# cs301_07b.net
KiCad netlist of a schematic drawn in Altium Designer
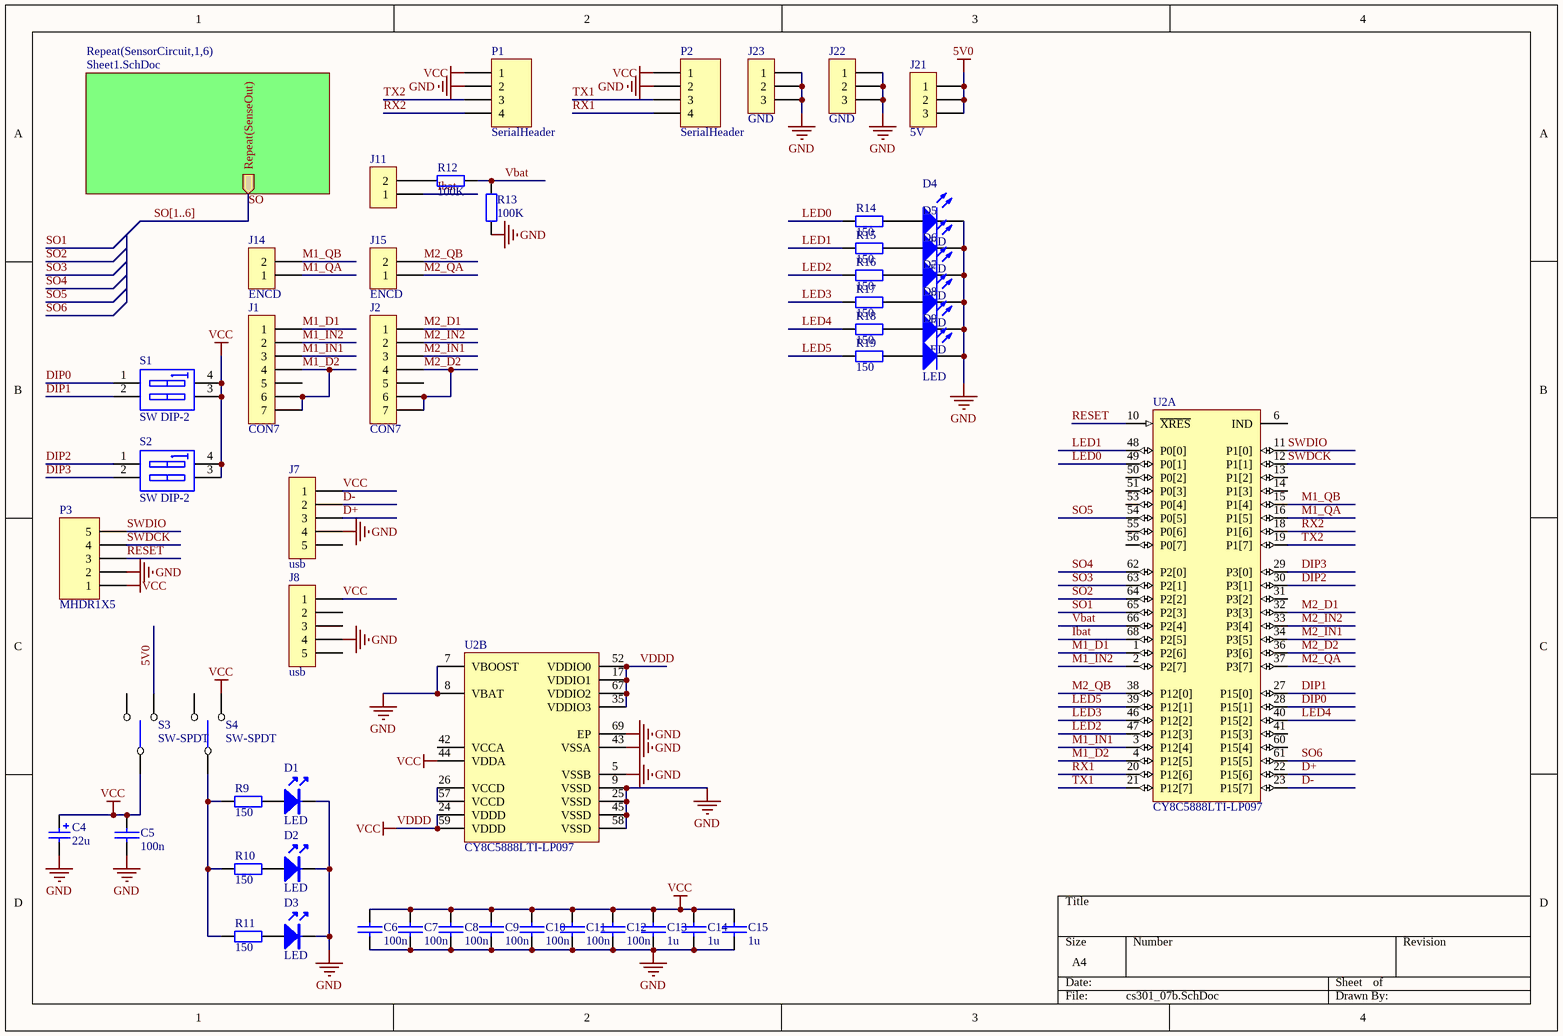
[diagram p0: cs301_07b.SchDoc]

(export (version "E")
  (design (tool "Eeschema 10.0.6"))
  (components
    (comp (ref "C4")
      (value "22u")
      (footprint "ECE-CAPAE6.3X5.4SM")
      (description "CAP 22uF 35V ELE SM")
      (libsource (lib "EceParts") (part "Cap Pol"))
    )
    (comp (ref "C5")
      (value "100n")
      (footprint "ECE-CAPC1608-0603SM")
      (description "CAP CER 100nF 25V X7R SM0603")
      (libsource (lib "EceParts") (part "Cap"))
    )
    (comp (ref "C6")
      (value "100n")
      (footprint "ECE-CAPC1608-0603SM")
      (description "CAP CER 100nF 25V X7R SM0603")
      (libsource (lib "EceParts") (part "Cap"))
    )
    (comp (ref "C7")
      (value "100n")
      (footprint "ECE-CAPC1608-0603SM")
      (description "CAP CER 100nF 25V X7R SM0603")
      (libsource (lib "EceParts") (part "Cap"))
    )
    (comp (ref "C8")
      (value "100n")
      (footprint "ECE-CAPC1608-0603SM")
      (description "CAP CER 100nF 25V X7R SM0603")
      (libsource (lib "EceParts") (part "Cap"))
    )
    (comp (ref "C9")
      (value "100n")
      (footprint "ECE-CAPC1608-0603SM")
      (description "CAP CER 100nF 25V X7R SM0603")
      (libsource (lib "EceParts") (part "Cap"))
    )
    (comp (ref "C10")
      (value "100n")
      (footprint "ECE-CAPC1608-0603SM")
      (description "CAP CER 100nF 25V X7R SM0603")
      (libsource (lib "EceParts") (part "Cap"))
    )
    (comp (ref "C11")
      (value "100n")
      (footprint "ECE-CAPC1608-0603SM")
      (description "CAP CER 100nF 25V X7R SM0603")
      (libsource (lib "EceParts") (part "Cap"))
    )
    (comp (ref "C12")
      (value "100n")
      (footprint "ECE-CAPC1608-0603SM")
      (description "CAP CER 100nF 25V X7R SM0603")
      (libsource (lib "EceParts") (part "Cap"))
    )
    (comp (ref "C13")
      (value "1u")
      (footprint "ECE-CAPC1608-0603SM")
      (description "CAP CER 1uF 50V X7R SM0603")
      (libsource (lib "EceParts") (part "Cap"))
    )
    (comp (ref "C14")
      (value "1u")
      (footprint "ECE-CAPC1608-0603SM")
      (description "CAP CER 1uF 50V X7R SM0603")
      (libsource (lib "EceParts") (part "Cap"))
    )
    (comp (ref "C15")
      (value "1u")
      (footprint "ECE-CAPC1608-0603SM")
      (description "CAP CER 1uF 50V X7R SM0603")
      (libsource (lib "EceParts") (part "Cap"))
    )
    (comp (ref "D1") (value "LED") (footprint "LED0.1/5MM") (libsource (lib "COMSYS301_2013") (part "LED")))
    (comp (ref "D2") (value "LED") (footprint "LED0.1/5MM") (libsource (lib "COMSYS301_2013") (part "LED")))
    (comp (ref "D3") (value "LED") (footprint "LED0.1/5MM") (libsource (lib "COMSYS301_2013") (part "LED")))
    (comp (ref "D4")
      (value "LED")
      (footprint "ECE-LED2012-0805SM")
      (description "LED RED ORANGE CLEAR 0805 SMD")
      (libsource (lib "EceParts") (part "LED"))
    )
    (comp (ref "D5")
      (value "LED")
      (footprint "ECE-LED2012-0805SM")
      (description "LED RED ORANGE CLEAR 0805 SMD")
      (libsource (lib "EceParts") (part "LED"))
    )
    (comp (ref "D6")
      (value "LED")
      (footprint "ECE-LED2012-0805SM")
      (description "LED RED ORANGE CLEAR 0805 SMD")
      (libsource (lib "EceParts") (part "LED"))
    )
    (comp (ref "D7")
      (value "LED")
      (footprint "ECE-LED2012-0805SM")
      (description "LED RED ORANGE CLEAR 0805 SMD")
      (libsource (lib "EceParts") (part "LED"))
    )
    (comp (ref "D8")
      (value "LED")
      (footprint "ECE-LED2012-0805SM")
      (description "LED RED ORANGE CLEAR 0805 SMD")
      (libsource (lib "EceParts") (part "LED"))
    )
    (comp (ref "D9")
      (value "LED")
      (footprint "ECE-LED2012-0805SM")
      (description "LED RED ORANGE CLEAR 0805 SMD")
      (libsource (lib "EceParts") (part "LED"))
    )
    (comp (ref "J1")
      (value "CON7")
      (footprint "SIP7")
      (description "Connector")
      (libsource (lib "Miscellaneous Devices") (part "CON7"))
    )
    (comp (ref "J2")
      (value "CON7")
      (footprint "SIP7")
      (description "Connector")
      (libsource (lib "Miscellaneous Devices") (part "CON7"))
    )
    (comp (ref "J7")
      (value "usb")
      (footprint "SIP5")
      (description "Connector")
      (libsource (lib "Miscellaneous Devices") (part "CON5"))
    )
    (comp (ref "J8")
      (value "usb")
      (footprint "SIP5")
      (description "Connector")
      (libsource (lib "Miscellaneous Devices") (part "CON5"))
    )
    (comp (ref "J11")
      (value "Battery")
      (footprint "sip2")
      (description "Connector")
      (libsource (lib "Miscellaneous Devices") (part "CON2"))
    )
    (comp (ref "J14")
      (value "ENCD")
      (footprint "sip2")
      (description "Connector")
      (libsource (lib "Miscellaneous Devices") (part "CON2"))
    )
    (comp (ref "J15")
      (value "ENCD")
      (footprint "sip2")
      (description "Connector")
      (libsource (lib "Miscellaneous Devices") (part "CON2"))
    )
    (comp (ref "J21")
      (value "5V")
      (footprint "sip3")
      (description "Connector")
      (libsource (lib "Miscellaneous Devices") (part "CON3"))
    )
    (comp (ref "J22")
      (value "GND")
      (footprint "sip3")
      (description "Connector")
      (libsource (lib "Miscellaneous Devices") (part "CON3"))
    )
    (comp (ref "J23")
      (value "GND")
      (footprint "sip3")
      (description "Connector")
      (libsource (lib "Miscellaneous Devices") (part "CON3"))
    )
    (comp (ref "P1")
      (value "SerialHeader")
      (footprint "HDR1X4")
      (description "Header, 4-Pin")
      (fields (field (name "PUBLISHER") "Altium Limited"))
      (libsource (lib "Miscellaneous Connectors") (part "Header 4"))
    )
    (comp (ref "P2")
      (value "SerialHeader")
      (footprint "HDR1X4")
      (description "Header, 4-Pin")
      (fields (field (name "PUBLISHER") "Altium Limited"))
      (libsource (lib "Miscellaneous Connectors") (part "Header 4"))
    )
    (comp (ref "P3")
      (value "MHDR1X5")
      (footprint "MHDR1X5")
      (description "Header, 5-Pin")
      (fields (field (name "PUBLISHER") "Altium Limited"))
      (libsource (lib "Miscellaneous Connectors") (part "MHDR1X5"))
    )
    (comp (ref "R9")
      (value "150")
      (footprint "ECE-RESC1608-0603SM")
      (description "RES CER 150R 1608 SM")
      (libsource (lib "EceParts") (part "Resistor"))
    )
    (comp (ref "R10")
      (value "150")
      (footprint "ECE-RESC1608-0603SM")
      (description "RES CER 150R 1608 SM")
      (libsource (lib "EceParts") (part "Resistor"))
    )
    (comp (ref "R11")
      (value "150")
      (footprint "ECE-RESC1608-0603SM")
      (description "RES CER 150R 1608 SM")
      (libsource (lib "EceParts") (part "Resistor"))
    )
    (comp (ref "R12")
      (value "100K")
      (footprint "ECE-RESC1608-0603SM")
      (description "RES CER 100K 1608 SM")
      (libsource (lib "EceParts") (part "Resistor"))
    )
    (comp (ref "R13")
      (value "100K")
      (footprint "ECE-RESC1608-0603SM")
      (description "RES CER 100K 1608 SM")
      (libsource (lib "") (part "Resistor_1"))
    )
    (comp (ref "R14")
      (value "150")
      (footprint "ECE-RESC1608-0603SM")
      (description "RES CER 150R 1608 SM")
      (libsource (lib "EceParts") (part "Resistor"))
    )
    (comp (ref "R15")
      (value "150")
      (footprint "ECE-RESC1608-0603SM")
      (description "RES CER 150R 1608 SM")
      (libsource (lib "EceParts") (part "Resistor"))
    )
    (comp (ref "R16")
      (value "150")
      (footprint "ECE-RESC1608-0603SM")
      (description "RES CER 150R 1608 SM")
      (libsource (lib "EceParts") (part "Resistor"))
    )
    (comp (ref "R17")
      (value "150")
      (footprint "ECE-RESC1608-0603SM")
      (description "RES CER 150R 1608 SM")
      (libsource (lib "EceParts") (part "Resistor"))
    )
    (comp (ref "R18")
      (value "150")
      (footprint "ECE-RESC1608-0603SM")
      (description "RES CER 150R 1608 SM")
      (libsource (lib "EceParts") (part "Resistor"))
    )
    (comp (ref "R19")
      (value "150")
      (footprint "ECE-RESC1608-0603SM")
      (description "RES CER 150R 1608 SM")
      (libsource (lib "EceParts") (part "Resistor"))
    )
    (comp (ref "S1")
      (value "SW DIP-2")
      (footprint "DIP-4")
      (description "DIP Switch, 2 Position, SPST")
      (fields (field (name "PUBLISHER") "Altium Limited"))
      (libsource (lib "Miscellaneous Devices") (part "SW DIP-2"))
    )
    (comp (ref "S2")
      (value "SW DIP-2")
      (footprint "DIP-4")
      (description "DIP Switch, 2 Position, SPST")
      (fields (field (name "PUBLISHER") "Altium Limited"))
      (libsource (lib "Miscellaneous Devices") (part "SW DIP-2"))
    )
    (comp (ref "S3")
      (value "SW-SPDT")
      (footprint "SW-SPDT")
      (description "Toggle Switch")
      (libsource (lib "COMSYS301_2013") (part "SW-SPDT"))
    )
    (comp (ref "S4")
      (value "SW-SPDT")
      (footprint "SW-SPDT")
      (description "Toggle Switch")
      (libsource (lib "COMSYS301_2013") (part "SW-SPDT"))
    )
    (comp (ref "U2")
      (value "CY8C5888LTI-LP097")
      (footprint "CYP-LTX68_N")
      (description "PSoC Programmable System-on-Chip, 256 KB Flash, 38 GPIOs, 1.71 to 5.5 V, 68-Pin QFN (LTX68), Tray")
      (fields (field (name "MANUFACTURER") "Cypress"))
      (libsource (lib "Cypress PSoC 5LP") (part "CY8C5888LTI-LP097"))
    )
  )
  (nets
    (net (code "1") (name "/D+") (class "Default")
      (node (ref "J7") (pin "3") (pinfunction "3_3") (pintype "passive"))
      (node (ref "U2") (pin "22") (pinfunction "P15[6]_22") (pintype "bidirectional"))
    )
    (net (code "2") (name "/D-") (class "Default")
      (node (ref "J7") (pin "2") (pinfunction "2_2") (pintype "passive"))
      (node (ref "U2") (pin "23") (pinfunction "P15[7]_23") (pintype "bidirectional"))
    )
    (net (code "3") (name "/DIP0") (class "Default")
      (node (ref "S1") (pin "1") (pinfunction "A1_1") (pintype "passive"))
      (node (ref "U2") (pin "28") (pinfunction "P15[1]_28") (pintype "bidirectional"))
    )
    (net (code "4") (name "/DIP1") (class "Default")
      (node (ref "S1") (pin "2") (pinfunction "A2_2") (pintype "passive"))
      (node (ref "U2") (pin "27") (pinfunction "P15[0]_27") (pintype "bidirectional"))
    )
    (net (code "5") (name "/DIP2") (class "Default")
      (node (ref "S2") (pin "1") (pinfunction "A1_1") (pintype "passive"))
      (node (ref "U2") (pin "30") (pinfunction "P3[1]_30") (pintype "bidirectional"))
    )
    (net (code "6") (name "/DIP3") (class "Default")
      (node (ref "S2") (pin "2") (pinfunction "A2_2") (pintype "passive"))
      (node (ref "U2") (pin "29") (pinfunction "P3[0]_29") (pintype "bidirectional"))
    )
    (net (code "7") (name "/Ibat") (class "Default")
      (node (ref "J11") (pin "1") (pinfunction "1_1") (pintype "passive"))
      (node (ref "U2") (pin "68") (pinfunction "P2[5]_68") (pintype "bidirectional"))
    )
    (net (code "8") (name "/LED0") (class "Default")
      (node (ref "R14") (pin "1") (pinfunction "1_1") (pintype "passive"))
      (node (ref "U2") (pin "49") (pinfunction "P0[1]_49") (pintype "bidirectional"))
    )
    (net (code "9") (name "/LED1") (class "Default")
      (node (ref "R15") (pin "1") (pinfunction "1_1") (pintype "passive"))
      (node (ref "U2") (pin "48") (pinfunction "P0[0]_48") (pintype "bidirectional"))
    )
    (net (code "10") (name "/LED2") (class "Default")
      (node (ref "R16") (pin "1") (pinfunction "1_1") (pintype "passive"))
      (node (ref "U2") (pin "47") (pinfunction "P12[3]_47") (pintype "bidirectional"))
    )
    (net (code "11") (name "/LED3") (class "Default")
      (node (ref "R17") (pin "1") (pinfunction "1_1") (pintype "passive"))
      (node (ref "U2") (pin "46") (pinfunction "P12[2]_46") (pintype "bidirectional"))
    )
    (net (code "12") (name "/LED4") (class "Default")
      (node (ref "R18") (pin "1") (pinfunction "1_1") (pintype "passive"))
      (node (ref "U2") (pin "40") (pinfunction "P15[2]_40") (pintype "bidirectional"))
    )
    (net (code "13") (name "/LED5") (class "Default")
      (node (ref "R19") (pin "1") (pinfunction "1_1") (pintype "passive"))
      (node (ref "U2") (pin "39") (pinfunction "P12[1]_39") (pintype "bidirectional"))
    )
    (net (code "14") (name "/M1_D1") (class "Default")
      (node (ref "J1") (pin "1") (pinfunction "1_1") (pintype "passive"))
      (node (ref "U2") (pin "1") (pinfunction "P2[6]_1") (pintype "bidirectional"))
    )
    (net (code "15") (name "/M1_D2") (class "Default")
      (node (ref "J1") (pin "4") (pinfunction "4_4") (pintype "passive"))
      (node (ref "J1") (pin "6") (pinfunction "6_6") (pintype "passive"))
      (node (ref "J1") (pin "7") (pinfunction "7_7") (pintype "passive"))
      (node (ref "U2") (pin "4") (pinfunction "P12[5]_4") (pintype "bidirectional"))
    )
    (net (code "16") (name "/M1_IN1") (class "Default")
      (node (ref "J1") (pin "3") (pinfunction "3_3") (pintype "passive"))
      (node (ref "U2") (pin "3") (pinfunction "P12[4]_3") (pintype "bidirectional"))
    )
    (net (code "17") (name "/M1_IN2") (class "Default")
      (node (ref "J1") (pin "2") (pinfunction "2_2") (pintype "passive"))
      (node (ref "U2") (pin "2") (pinfunction "P2[7]_2") (pintype "bidirectional"))
    )
    (net (code "18") (name "/M1_QA") (class "Default")
      (node (ref "J14") (pin "1") (pinfunction "1_1") (pintype "passive"))
      (node (ref "U2") (pin "16") (pinfunction "P1[5]_16") (pintype "bidirectional"))
    )
    (net (code "19") (name "/M1_QB") (class "Default")
      (node (ref "J14") (pin "2") (pinfunction "2_2") (pintype "passive"))
      (node (ref "U2") (pin "15") (pinfunction "P1[4]_15") (pintype "bidirectional"))
    )
    (net (code "20") (name "/M2_D1") (class "Default")
      (node (ref "J2") (pin "1") (pinfunction "1_1") (pintype "passive"))
      (node (ref "U2") (pin "32") (pinfunction "P3[3]_32") (pintype "bidirectional"))
    )
    (net (code "21") (name "/M2_D2") (class "Default")
      (node (ref "J2") (pin "4") (pinfunction "4_4") (pintype "passive"))
      (node (ref "J2") (pin "6") (pinfunction "6_6") (pintype "passive"))
      (node (ref "J2") (pin "7") (pinfunction "7_7") (pintype "passive"))
      (node (ref "U2") (pin "36") (pinfunction "P3[6]_36") (pintype "bidirectional"))
    )
    (net (code "22") (name "/M2_IN1") (class "Default")
      (node (ref "J2") (pin "3") (pinfunction "3_3") (pintype "passive"))
      (node (ref "U2") (pin "34") (pinfunction "P3[5]_34") (pintype "bidirectional"))
    )
    (net (code "23") (name "/M2_IN2") (class "Default")
      (node (ref "J2") (pin "2") (pinfunction "2_2") (pintype "passive"))
      (node (ref "U2") (pin "33") (pinfunction "P3[4]_33") (pintype "bidirectional"))
    )
    (net (code "24") (name "/M2_QA") (class "Default")
      (node (ref "J15") (pin "1") (pinfunction "1_1") (pintype "passive"))
      (node (ref "U2") (pin "37") (pinfunction "P3[7]_37") (pintype "bidirectional"))
    )
    (net (code "25") (name "/M2_QB") (class "Default")
      (node (ref "J15") (pin "2") (pinfunction "2_2") (pintype "passive"))
      (node (ref "U2") (pin "38") (pinfunction "P12[0]_38") (pintype "bidirectional"))
    )
    (net (code "26") (name "/RESET") (class "Default")
      (node (ref "P3") (pin "3") (pinfunction "3_3") (pintype "passive"))
      (node (ref "U2") (pin "10") (pinfunction "~{XRES}_10") (pintype "input"))
    )
    (net (code "27") (name "/RX1") (class "Default")
      (node (ref "P2") (pin "4") (pinfunction "4_4") (pintype "passive"))
      (node (ref "U2") (pin "20") (pinfunction "P12[6]_20") (pintype "bidirectional"))
    )
    (net (code "28") (name "/RX2") (class "Default")
      (node (ref "P1") (pin "4") (pinfunction "4_4") (pintype "passive"))
      (node (ref "U2") (pin "18") (pinfunction "P1[6]_18") (pintype "bidirectional"))
    )
    (net (code "30") (name "/SO1") (class "Default")
      (node (ref "U2") (pin "65") (pinfunction "P2[3]_65") (pintype "bidirectional"))
    )
    (net (code "31") (name "/SO2") (class "Default")
      (node (ref "U2") (pin "64") (pinfunction "P2[2]_64") (pintype "bidirectional"))
    )
    (net (code "32") (name "/SO3") (class "Default")
      (node (ref "U2") (pin "63") (pinfunction "P2[1]_63") (pintype "bidirectional"))
    )
    (net (code "33") (name "/SO4") (class "Default")
      (node (ref "U2") (pin "62") (pinfunction "P2[0]_62") (pintype "bidirectional"))
    )
    (net (code "34") (name "/SO5") (class "Default")
      (node (ref "U2") (pin "54") (pinfunction "P0[5]_54") (pintype "bidirectional"))
    )
    (net (code "35") (name "/SO6") (class "Default")
      (node (ref "U2") (pin "61") (pinfunction "P15[5]_61") (pintype "bidirectional"))
    )
    (net (code "37") (name "/SWDCK") (class "Default")
      (node (ref "P3") (pin "4") (pinfunction "4_4") (pintype "passive"))
      (node (ref "U2") (pin "12") (pinfunction "P1[1]_12") (pintype "bidirectional"))
    )
    (net (code "38") (name "/SWDIO") (class "Default")
      (node (ref "P3") (pin "5") (pinfunction "5_5") (pintype "passive"))
      (node (ref "U2") (pin "11") (pinfunction "P1[0]_11") (pintype "bidirectional"))
    )
    (net (code "39") (name "/TX1") (class "Default")
      (node (ref "P2") (pin "3") (pinfunction "3_3") (pintype "passive"))
      (node (ref "U2") (pin "21") (pinfunction "P12[7]_21") (pintype "bidirectional"))
    )
    (net (code "40") (name "/TX2") (class "Default")
      (node (ref "P1") (pin "3") (pinfunction "3_3") (pintype "passive"))
      (node (ref "U2") (pin "19") (pinfunction "P1[7]_19") (pintype "bidirectional"))
    )
    (net (code "41") (name "/Vbat") (class "Default")
      (node (ref "R12") (pin "2") (pinfunction "2_2") (pintype "passive"))
      (node (ref "R13") (pin "1") (pinfunction "1_1") (pintype "passive"))
      (node (ref "U2") (pin "66") (pinfunction "P2[4]_66") (pintype "bidirectional"))
    )
    (net (code "42") (name "5V0") (class "Default")
      (node (ref "J21") (pin "1") (pinfunction "1_1") (pintype "passive"))
      (node (ref "J21") (pin "2") (pinfunction "2_2") (pintype "passive"))
      (node (ref "J21") (pin "3") (pinfunction "3_3") (pintype "passive"))
      (node (ref "S3") (pin "3") (pinfunction "3_3") (pintype "passive"))
    )
    (net (code "43") (name "GND") (class "Default")
      (node (ref "C10") (pin "1") (pinfunction "1_1") (pintype "passive"))
      (node (ref "C11") (pin "1") (pinfunction "1_1") (pintype "passive"))
      (node (ref "C12") (pin "1") (pinfunction "1_1") (pintype "passive"))
      (node (ref "C13") (pin "1") (pinfunction "1_1") (pintype "passive"))
      (node (ref "C14") (pin "1") (pinfunction "1_1") (pintype "passive"))
      (node (ref "C15") (pin "1") (pinfunction "1_1") (pintype "passive"))
      (node (ref "C4") (pin "2") (pinfunction "2_2") (pintype "passive"))
      (node (ref "C5") (pin "1") (pinfunction "1_1") (pintype "passive"))
      (node (ref "C6") (pin "1") (pinfunction "1_1") (pintype "passive"))
      (node (ref "C7") (pin "1") (pinfunction "1_1") (pintype "passive"))
      (node (ref "C8") (pin "1") (pinfunction "1_1") (pintype "passive"))
      (node (ref "C9") (pin "1") (pinfunction "1_1") (pintype "passive"))
      (node (ref "D1") (pin "K") (pinfunction "2_K") (pintype "passive"))
      (node (ref "D2") (pin "K") (pinfunction "2_K") (pintype "passive"))
      (node (ref "D3") (pin "K") (pinfunction "2_K") (pintype "passive"))
      (node (ref "D4") (pin "2") (pinfunction "K_2") (pintype "passive"))
      (node (ref "D5") (pin "2") (pinfunction "K_2") (pintype "passive"))
      (node (ref "D6") (pin "2") (pinfunction "K_2") (pintype "passive"))
      (node (ref "D7") (pin "2") (pinfunction "K_2") (pintype "passive"))
      (node (ref "D8") (pin "2") (pinfunction "K_2") (pintype "passive"))
      (node (ref "D9") (pin "2") (pinfunction "K_2") (pintype "passive"))
      (node (ref "J22") (pin "1") (pinfunction "1_1") (pintype "passive"))
      (node (ref "J22") (pin "2") (pinfunction "2_2") (pintype "passive"))
      (node (ref "J22") (pin "3") (pinfunction "3_3") (pintype "passive"))
      (node (ref "J23") (pin "1") (pinfunction "1_1") (pintype "passive"))
      (node (ref "J23") (pin "2") (pinfunction "2_2") (pintype "passive"))
      (node (ref "J23") (pin "3") (pinfunction "3_3") (pintype "passive"))
      (node (ref "J7") (pin "4") (pinfunction "4_4") (pintype "passive"))
      (node (ref "J8") (pin "4") (pinfunction "4_4") (pintype "passive"))
      (node (ref "P1") (pin "2") (pinfunction "2_2") (pintype "passive"))
      (node (ref "P2") (pin "2") (pinfunction "2_2") (pintype "passive"))
      (node (ref "P3") (pin "2") (pinfunction "2_2") (pintype "passive"))
      (node (ref "R13") (pin "2") (pinfunction "2_2") (pintype "passive"))
      (node (ref "U2") (pin "25") (pinfunction "VSSD_25") (pintype "power_in"))
      (node (ref "U2") (pin "43") (pinfunction "VSSA_43") (pintype "power_in"))
      (node (ref "U2") (pin "45") (pinfunction "VSSD_45") (pintype "power_in"))
      (node (ref "U2") (pin "5") (pinfunction "VSSB_5") (pintype "power_in"))
      (node (ref "U2") (pin "58") (pinfunction "VSSD_58") (pintype "power_in"))
      (node (ref "U2") (pin "69") (pinfunction "EP_69") (pintype "power_in"))
      (node (ref "U2") (pin "7") (pinfunction "VBOOST_7") (pintype "power_in"))
      (node (ref "U2") (pin "8") (pinfunction "VBAT_8") (pintype "power_in"))
      (node (ref "U2") (pin "9") (pinfunction "VSSD_9") (pintype "power_in"))
    )
    (net (code "44") (name "Net-(D1-1)") (class "Default")
      (node (ref "D1") (pin "A") (pinfunction "1_A") (pintype "passive"))
      (node (ref "R9") (pin "2") (pinfunction "2_2") (pintype "passive"))
    )
    (net (code "45") (name "Net-(D2-1)") (class "Default")
      (node (ref "D2") (pin "A") (pinfunction "1_A") (pintype "passive"))
      (node (ref "R10") (pin "2") (pinfunction "2_2") (pintype "passive"))
    )
    (net (code "46") (name "Net-(D3-1)") (class "Default")
      (node (ref "D3") (pin "A") (pinfunction "1_A") (pintype "passive"))
      (node (ref "R11") (pin "2") (pinfunction "2_2") (pintype "passive"))
    )
    (net (code "47") (name "Net-(D4-A)") (class "Default")
      (node (ref "D4") (pin "1") (pinfunction "A_1") (pintype "passive"))
      (node (ref "R14") (pin "2") (pinfunction "2_2") (pintype "passive"))
    )
    (net (code "48") (name "Net-(D5-A)") (class "Default")
      (node (ref "D5") (pin "1") (pinfunction "A_1") (pintype "passive"))
      (node (ref "R15") (pin "2") (pinfunction "2_2") (pintype "passive"))
    )
    (net (code "49") (name "Net-(D6-A)") (class "Default")
      (node (ref "D6") (pin "1") (pinfunction "A_1") (pintype "passive"))
      (node (ref "R16") (pin "2") (pinfunction "2_2") (pintype "passive"))
    )
    (net (code "50") (name "Net-(D7-A)") (class "Default")
      (node (ref "D7") (pin "1") (pinfunction "A_1") (pintype "passive"))
      (node (ref "R17") (pin "2") (pinfunction "2_2") (pintype "passive"))
    )
    (net (code "51") (name "Net-(D8-A)") (class "Default")
      (node (ref "D8") (pin "1") (pinfunction "A_1") (pintype "passive"))
      (node (ref "R18") (pin "2") (pinfunction "2_2") (pintype "passive"))
    )
    (net (code "52") (name "Net-(D9-A)") (class "Default")
      (node (ref "D9") (pin "1") (pinfunction "A_1") (pintype "passive"))
      (node (ref "R19") (pin "2") (pinfunction "2_2") (pintype "passive"))
    )
    (net (code "53") (name "Net-(J11-Pad2)") (class "Default")
      (node (ref "J11") (pin "2") (pinfunction "2_2") (pintype "passive"))
      (node (ref "R12") (pin "1") (pinfunction "1_1") (pintype "passive"))
    )
    (net (code "54") (name "Net-(R10-Pad1)") (class "Default")
      (node (ref "R10") (pin "1") (pinfunction "1_1") (pintype "passive"))
      (node (ref "R11") (pin "1") (pinfunction "1_1") (pintype "passive"))
      (node (ref "R9") (pin "1") (pinfunction "1_1") (pintype "passive"))
      (node (ref "S4") (pin "2") (pinfunction "2_2") (pintype "passive"))
    )
    (net (code "55") (name "Net-(U2B-VCCD-Pad26)") (class "Default")
      (node (ref "U2") (pin "26") (pinfunction "VCCD_26") (pintype "power_in"))
      (node (ref "U2") (pin "57") (pinfunction "VCCD_57") (pintype "power_in"))
    )
    (net (code "56") (name "VCC") (class "Default")
      (node (ref "C10") (pin "2") (pinfunction "2_2") (pintype "passive"))
      (node (ref "C11") (pin "2") (pinfunction "2_2") (pintype "passive"))
      (node (ref "C12") (pin "2") (pinfunction "2_2") (pintype "passive"))
      (node (ref "C13") (pin "2") (pinfunction "2_2") (pintype "passive"))
      (node (ref "C14") (pin "2") (pinfunction "2_2") (pintype "passive"))
      (node (ref "C15") (pin "2") (pinfunction "2_2") (pintype "passive"))
      (node (ref "C4") (pin "1") (pinfunction "1_1") (pintype "passive"))
      (node (ref "C5") (pin "2") (pinfunction "2_2") (pintype "passive"))
      (node (ref "C6") (pin "2") (pinfunction "2_2") (pintype "passive"))
      (node (ref "C7") (pin "2") (pinfunction "2_2") (pintype "passive"))
      (node (ref "C8") (pin "2") (pinfunction "2_2") (pintype "passive"))
      (node (ref "C9") (pin "2") (pinfunction "2_2") (pintype "passive"))
      (node (ref "J7") (pin "1") (pinfunction "1_1") (pintype "passive"))
      (node (ref "J8") (pin "1") (pinfunction "1_1") (pintype "passive"))
      (node (ref "P1") (pin "1") (pinfunction "1_1") (pintype "passive"))
      (node (ref "P2") (pin "1") (pinfunction "1_1") (pintype "passive"))
      (node (ref "P3") (pin "1") (pinfunction "1_1") (pintype "passive"))
      (node (ref "S1") (pin "3") (pinfunction "B2_3") (pintype "passive"))
      (node (ref "S1") (pin "4") (pinfunction "B1_4") (pintype "passive"))
      (node (ref "S2") (pin "3") (pinfunction "B2_3") (pintype "passive"))
      (node (ref "S2") (pin "4") (pinfunction "B1_4") (pintype "passive"))
      (node (ref "S3") (pin "2") (pinfunction "2_2") (pintype "passive"))
      (node (ref "S4") (pin "3") (pinfunction "3_3") (pintype "passive"))
      (node (ref "U2") (pin "17") (pinfunction "VDDIO1_17") (pintype "power_in"))
      (node (ref "U2") (pin "24") (pinfunction "VDDD_24") (pintype "power_in"))
      (node (ref "U2") (pin "35") (pinfunction "VDDIO3_35") (pintype "power_in"))
      (node (ref "U2") (pin "44") (pinfunction "VDDA_44") (pintype "power_in"))
      (node (ref "U2") (pin "52") (pinfunction "VDDIO0_52") (pintype "power_in"))
      (node (ref "U2") (pin "59") (pinfunction "VDDD_59") (pintype "power_in"))
      (node (ref "U2") (pin "67") (pinfunction "VDDIO2_67") (pintype "power_in"))
    )
    (net (code "57") (name "unconnected-(J1-Pad5)") (class "Default")
      (node (ref "J1") (pin "5") (pinfunction "5_5") (pintype "passive"))
    )
    (net (code "58") (name "unconnected-(J2-Pad5)") (class "Default")
      (node (ref "J2") (pin "5") (pinfunction "5_5") (pintype "passive"))
    )
    (net (code "59") (name "unconnected-(J7-Pad5)") (class "Default")
      (node (ref "J7") (pin "5") (pinfunction "5_5") (pintype "passive"))
    )
    (net (code "60") (name "unconnected-(J8-Pad2)") (class "Default")
      (node (ref "J8") (pin "2") (pinfunction "2_2") (pintype "passive"))
    )
    (net (code "61") (name "unconnected-(J8-Pad3)") (class "Default")
      (node (ref "J8") (pin "3") (pinfunction "3_3") (pintype "passive"))
    )
    (net (code "62") (name "unconnected-(J8-Pad5)") (class "Default")
      (node (ref "J8") (pin "5") (pinfunction "5_5") (pintype "passive"))
    )
    (net (code "63") (name "unconnected-(S3-Pad1)") (class "Default")
      (node (ref "S3") (pin "1") (pinfunction "1_1") (pintype "passive"))
    )
    (net (code "64") (name "unconnected-(S4-Pad1)") (class "Default")
      (node (ref "S4") (pin "1") (pinfunction "1_1") (pintype "passive"))
    )
    (net (code "65") (name "unconnected-(U2A-IND-Pad6)") (class "Default")
      (node (ref "U2") (pin "6") (pinfunction "IND_6") (pintype "passive"))
    )
    (net (code "66") (name "unconnected-(U2A-P0[2]-Pad50)") (class "Default")
      (node (ref "U2") (pin "50") (pinfunction "P0[2]_50") (pintype "bidirectional"))
    )
    (net (code "67") (name "unconnected-(U2A-P0[3]-Pad51)") (class "Default")
      (node (ref "U2") (pin "51") (pinfunction "P0[3]_51") (pintype "bidirectional"))
    )
    (net (code "68") (name "unconnected-(U2A-P0[4]-Pad53)") (class "Default")
      (node (ref "U2") (pin "53") (pinfunction "P0[4]_53") (pintype "bidirectional"))
    )
    (net (code "69") (name "unconnected-(U2A-P0[6]-Pad55)") (class "Default")
      (node (ref "U2") (pin "55") (pinfunction "P0[6]_55") (pintype "bidirectional"))
    )
    (net (code "70") (name "unconnected-(U2A-P0[7]-Pad56)") (class "Default")
      (node (ref "U2") (pin "56") (pinfunction "P0[7]_56") (pintype "bidirectional"))
    )
    (net (code "71") (name "unconnected-(U2A-P1[2]-Pad13)") (class "Default")
      (node (ref "U2") (pin "13") (pinfunction "P1[2]_13") (pintype "bidirectional"))
    )
    (net (code "72") (name "unconnected-(U2A-P1[3]-Pad14)") (class "Default")
      (node (ref "U2") (pin "14") (pinfunction "P1[3]_14") (pintype "bidirectional"))
    )
    (net (code "73") (name "unconnected-(U2A-P3[2]-Pad31)") (class "Default")
      (node (ref "U2") (pin "31") (pinfunction "P3[2]_31") (pintype "bidirectional"))
    )
    (net (code "74") (name "unconnected-(U2A-P15[3]-Pad41)") (class "Default")
      (node (ref "U2") (pin "41") (pinfunction "P15[3]_41") (pintype "bidirectional"))
    )
    (net (code "75") (name "unconnected-(U2A-P15[4]-Pad60)") (class "Default")
      (node (ref "U2") (pin "60") (pinfunction "P15[4]_60") (pintype "bidirectional"))
    )
    (net (code "76") (name "unconnected-(U2B-VCCA-Pad42)") (class "Default")
      (node (ref "U2") (pin "42") (pinfunction "VCCA_42") (pintype "power_in"))
    )
  )
)
